# vacuumsensor.net
KiCad netlist of a schematic drawn in EAGLE
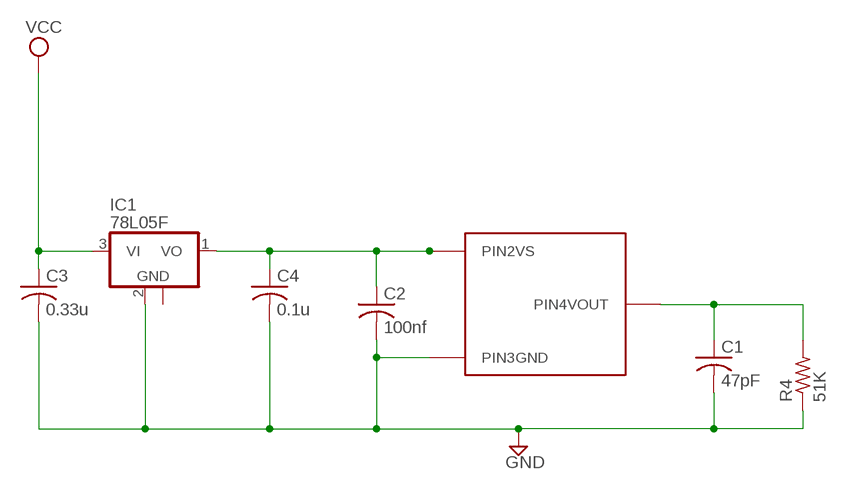
[diagram p0: schematic, sheet 1]

(export (version "E")
  (design (tool "Eeschema 10.0.6"))
  (components
    (comp (ref "C1")
      (value "47pF")
      (footprint "eagle-import:C050-024X044")
      (libsource (lib "eagle-import") (part "C-US050-024X044"))
    )
    (comp (ref "C2")
      (value "100nf")
      (footprint "eagle-import:C050-024X044")
      (libsource (lib "eagle-import") (part "C-US050-024X044"))
    )
    (comp (ref "C3")
      (value "0.33u")
      (footprint "eagle-import:C050-024X044")
      (libsource (lib "eagle-import") (part "C-US050-024X044"))
    )
    (comp (ref "C4")
      (value "0.1u")
      (footprint "eagle-import:C050-024X044")
      (libsource (lib "eagle-import") (part "C-US050-024X044"))
    )
    (comp (ref "IC1")
      (value "78L05F")
      (footprint "eagle-import:SOT89")
      (libsource (lib "eagle-import") (part "78LF05"))
    )
    (comp (ref "R4")
      (value "51K")
      (footprint "eagle-import:0309_12")
      (libsource (lib "eagle-import") (part "R-US_0309/12"))
    )
    (comp (ref "U$1")
      (value "MPXV6115V6U")
      (footprint "eagle-import:482A")
      (libsource (lib "eagle-import") (part "MPXV6115V6U"))
    )
  )
  (nets
    (net (code "1") (name "GND") (class "Default")
      (node (ref "C1") (pin "2") (pinfunction "2_2") (pintype "passive"))
      (node (ref "C2") (pin "2") (pinfunction "2_2") (pintype "passive"))
      (node (ref "C3") (pin "2") (pinfunction "2_2") (pintype "passive"))
      (node (ref "C4") (pin "2") (pinfunction "2_2") (pintype "passive"))
      (node (ref "IC1") (pin "2") (pinfunction "GND_2") (pintype "passive"))
      (node (ref "R4") (pin "1") (pinfunction "1_1") (pintype "passive"))
      (node (ref "U$1") (pin "P$3") (pinfunction "PIN3GND_P$3") (pintype "bidirectional"))
    )
    (net (code "2") (name "Net-(IC1-VO)") (class "Default")
      (node (ref "C2") (pin "1") (pinfunction "1_1") (pintype "passive"))
      (node (ref "C4") (pin "1") (pinfunction "1_1") (pintype "passive"))
      (node (ref "IC1") (pin "1") (pinfunction "VO_1") (pintype "passive"))
      (node (ref "U$1") (pin "P$2") (pinfunction "PIN2VS_P$2") (pintype "power_in"))
    )
    (net (code "3") (name "Net-(U$1-PIN4VOUT)") (class "Default")
      (node (ref "C1") (pin "1") (pinfunction "1_1") (pintype "passive"))
      (node (ref "R4") (pin "2") (pinfunction "2_2") (pintype "passive"))
      (node (ref "U$1") (pin "P$4") (pinfunction "PIN4VOUT_P$4") (pintype "bidirectional"))
    )
    (net (code "4") (name "VCC") (class "Default")
      (node (ref "C3") (pin "1") (pinfunction "1_1") (pintype "passive"))
      (node (ref "IC1") (pin "3") (pinfunction "VI_3") (pintype "input"))
    )
    (net (code "5") (name "unconnected-(IC1-GND-Pad2@1)") (class "Default")
      (node (ref "IC1") (pin "2@1") (pinfunction "GND_2@1") (pintype "passive"))
    )
  )
)
